# AQM_V1_Rev2.net
KiCad netlist of a schematic drawn in EasyEDA Pro
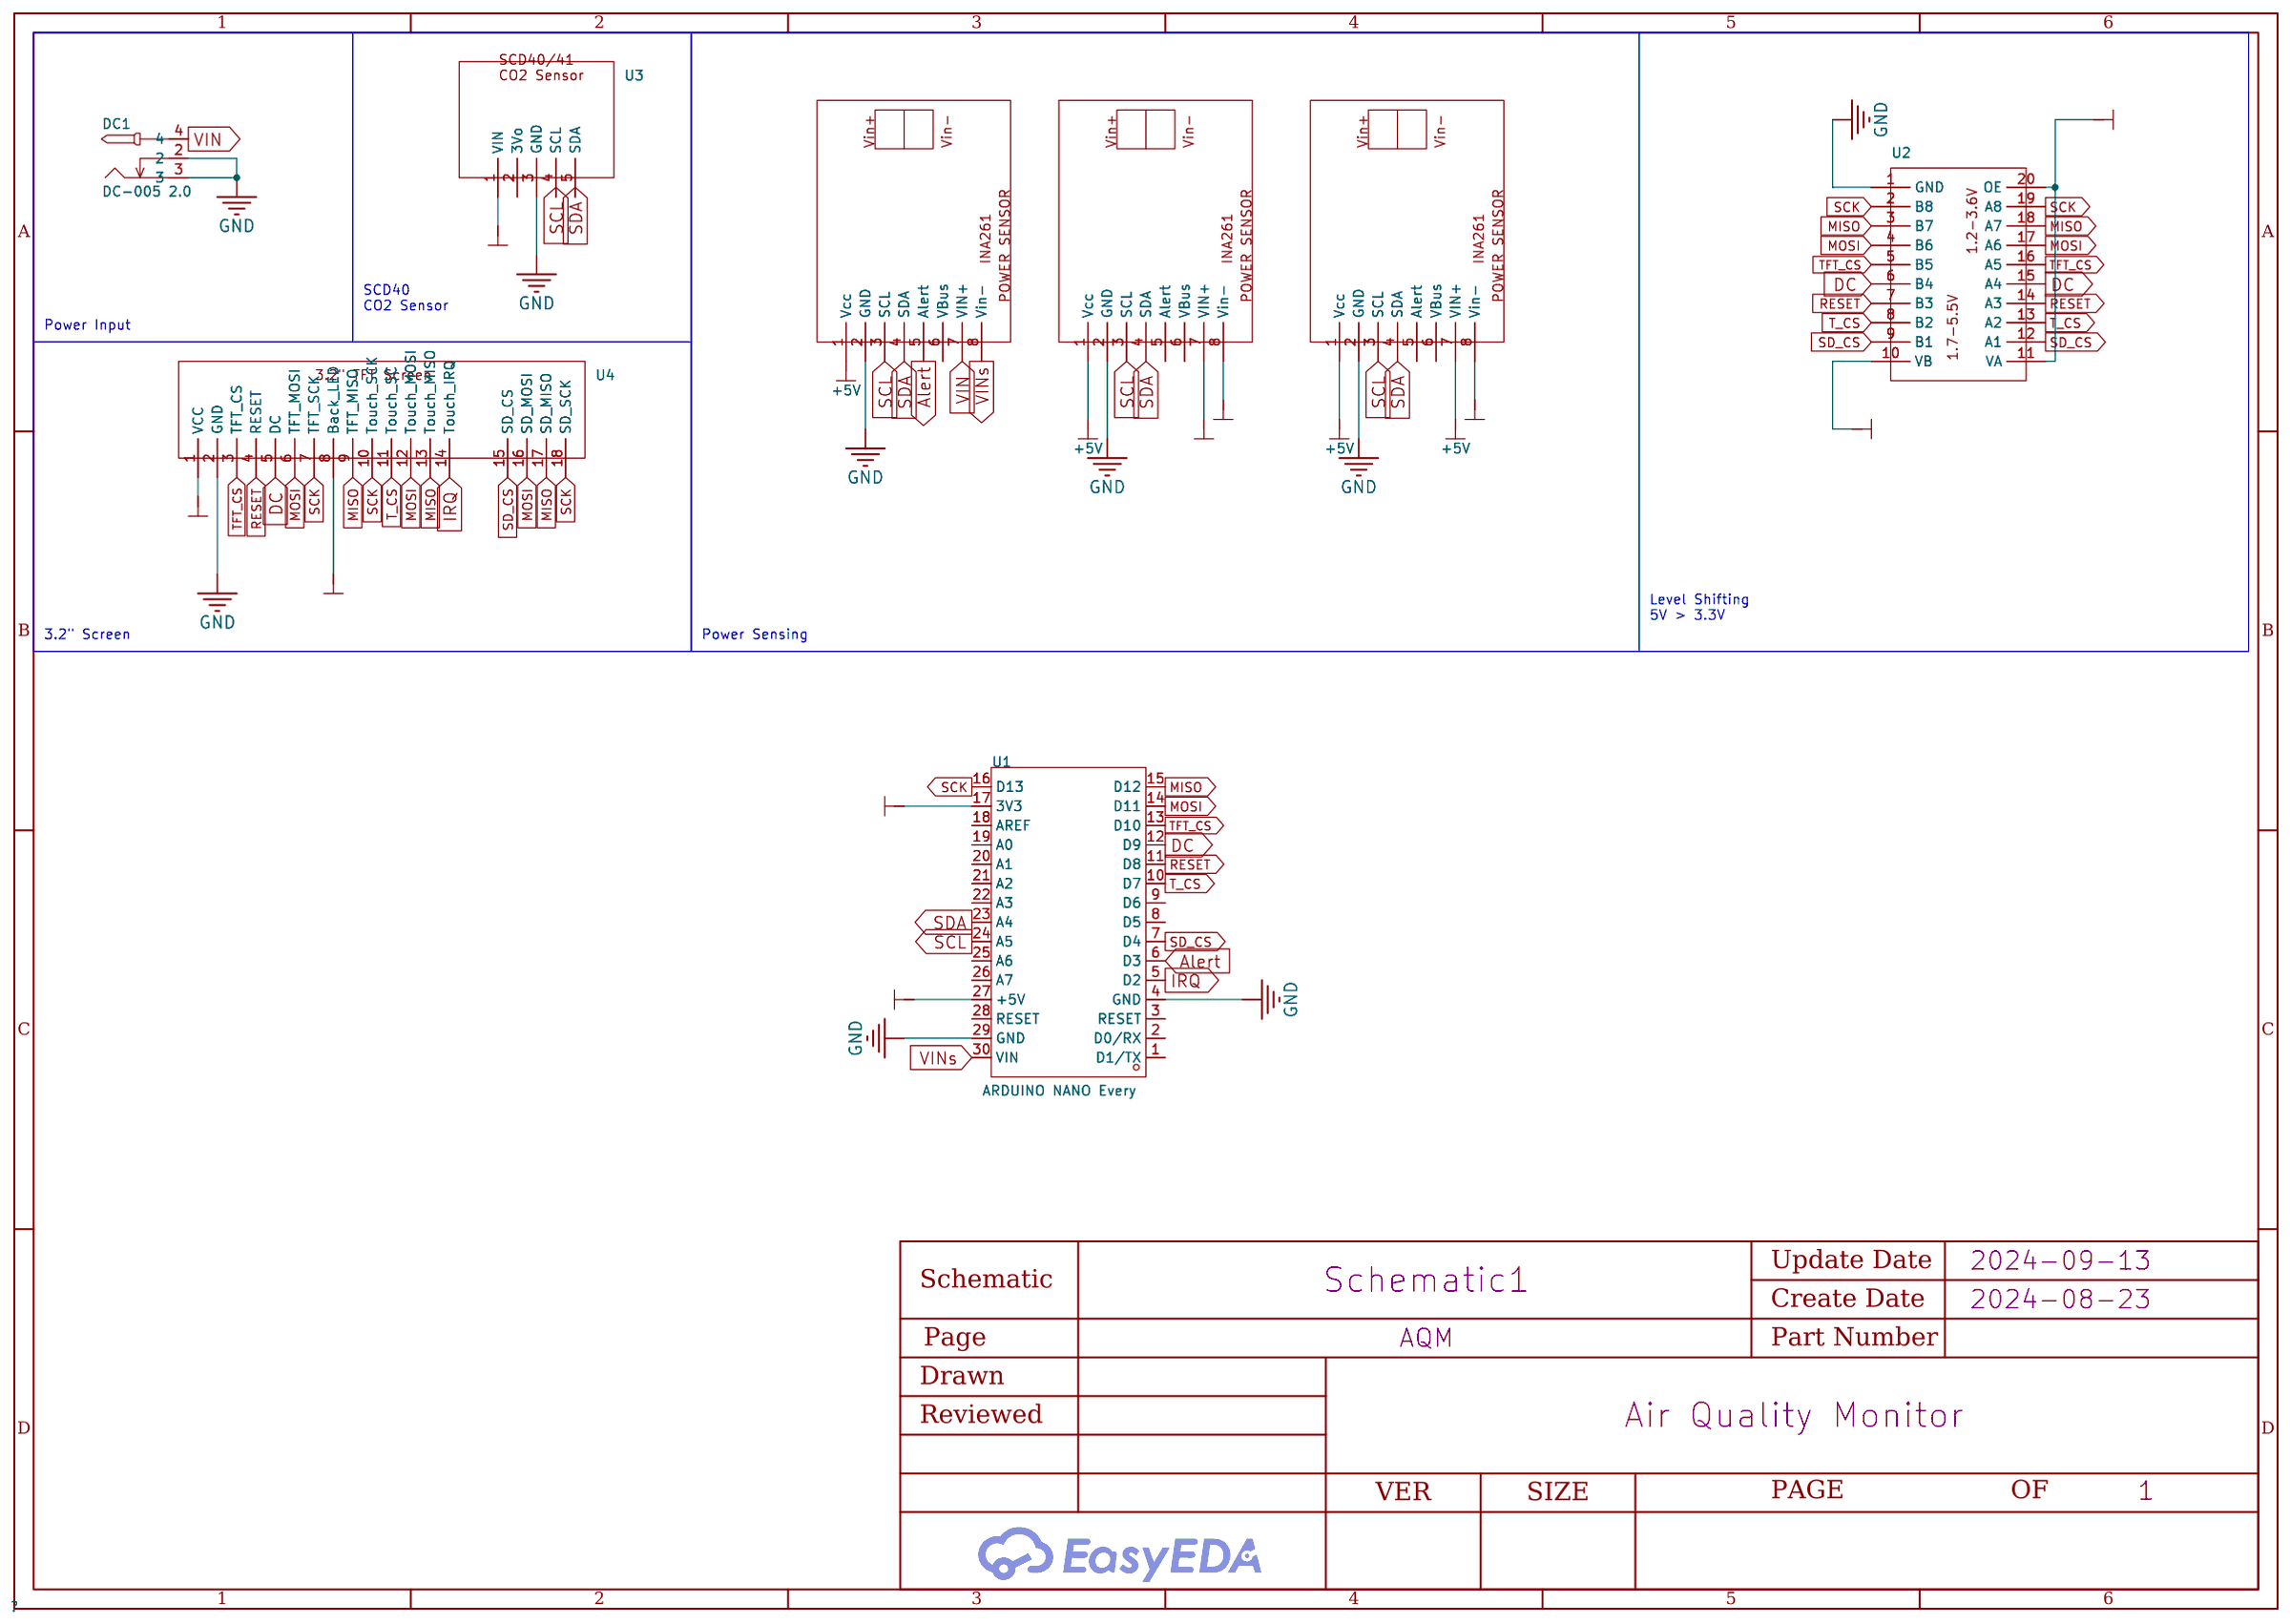
[diagram p0: schematic sheet]

(export (version "E")
  (design (tool "Eeschema 10.0.6"))
  (components
    (comp (ref "3.3V")
      (value "~")
      (footprint "easyedapro:INA260 Breakout")
      (description "Adafruit INA260 High or Low Side Voltage, Current, Power Sensor")
      (libsource (lib "easyedapro") (part "INA260 Breakout"))
    )
    (comp (ref "5V")
      (value "~")
      (footprint "easyedapro:INA260 Breakout")
      (description "Adafruit INA260 High or Low Side Voltage, Current, Power Sensor")
      (libsource (lib "easyedapro") (part "INA260 Breakout"))
    )
    (comp (ref "DC1")
      (value "DC-005 2.0")
      (footprint "easyedapro:DC-IN-TH_DC-5520-1")
      (fields (field (name "Manufacturer") "BOOMELE(博穆精密)"))
      (libsource (lib "easyedapro") (part "DC-005 5.5-2.0MM"))
    )
    (comp (ref "U1")
      (value "ARDUINO NANO Every")
      (footprint "easyedapro:COMM-TH_ARDUINO_NANO")
      (libsource (lib "easyedapro") (part "ARDUINO_NANO"))
    )
    (comp (ref "U2")
      (value "~")
      (footprint "easyedapro:8 Channel Level Shifter Footprint")
      (description "Level Shifter for 8 Channels from 3.3V to 5V")
      (libsource (lib "easyedapro") (part "8 Channel Level Shifter Symbol"))
    )
    (comp (ref "U3")
      (value "~")
      (footprint "easyedapro:Adafruit SCD40/41")
      (libsource (lib "easyedapro") (part "Adafruit SCD40/41 Breakout"))
    )
    (comp (ref "U4")
      (value "~")
      (footprint "easyedapro:2.8\" TFT Display Footprint 1")
      (description "2.8\" TFT Screen with SPI, Touch and SD Card.")
      (libsource (lib "easyedapro") (part "3.2{dblquote} TFT Screen Symbol"))
    )
    (comp (ref "VIN")
      (value "~")
      (footprint "easyedapro:INA260 Breakout")
      (description "Adafruit INA260 High or Low Side Voltage, Current, Power Sensor")
      (libsource (lib "easyedapro") (part "INA260 Breakout"))
    )
  )
  (nets
    (net (code "1") (name "+3V") (class "Default")
      (node (ref "3.3V") (pin "7") (pinfunction "VIN+_7") (pintype "input"))
      (node (ref "U1") (pin "17") (pinfunction "3V3_17") (pintype "unspecified"))
    )
    (net (code "2") (name "+3VS") (class "Default")
      (node (ref "3.3V") (pin "8") (pinfunction "Vin-_8") (pintype "input"))
      (node (ref "U2") (pin "11") (pinfunction "VA_11") (pintype "input"))
      (node (ref "U2") (pin "20") (pinfunction "OE_20") (pintype "input"))
      (node (ref "U4") (pin "8") (pinfunction "Back_LED_8") (pintype "input"))
    )
    (net (code "3") (name "+5V") (class "Default")
      (node (ref "3.3V") (pin "1") (pinfunction "Vcc_1") (pintype "input"))
      (node (ref "5V") (pin "1") (pinfunction "Vcc_1") (pintype "input"))
      (node (ref "5V") (pin "7") (pinfunction "VIN+_7") (pintype "input"))
      (node (ref "U1") (pin "27") (pinfunction "+5V_27") (pintype "unspecified"))
      (node (ref "VIN") (pin "1") (pinfunction "Vcc_1") (pintype "input"))
    )
    (net (code "4") (name "+5VS") (class "Default")
      (node (ref "5V") (pin "8") (pinfunction "Vin-_8") (pintype "input"))
      (node (ref "U2") (pin "10") (pinfunction "VB_10") (pintype "input"))
      (node (ref "U3") (pin "1") (pinfunction "VIN_1") (pintype "input"))
      (node (ref "U4") (pin "1") (pinfunction "VCC_1") (pintype "input"))
    )
    (net (code "5") (name "Alert") (class "Default")
      (node (ref "U1") (pin "6") (pinfunction "D3_6") (pintype "unspecified"))
      (node (ref "VIN") (pin "5") (pinfunction "Alert_5") (pintype "input"))
    )
    (net (code "6") (name "DC") (class "Default")
      (node (ref "U1") (pin "12") (pinfunction "D9_12") (pintype "unspecified"))
      (node (ref "U2") (pin "15") (pinfunction "A4_15") (pintype "input"))
      (node (ref "U2") (pin "6") (pinfunction "B4_6") (pintype "input"))
      (node (ref "U4") (pin "5") (pinfunction "DC_5") (pintype "input"))
    )
    (net (code "7") (name "GND") (class "Default")
      (node (ref "3.3V") (pin "2") (pinfunction "GND_2") (pintype "input"))
      (node (ref "5V") (pin "2") (pinfunction "GND_2") (pintype "input"))
      (node (ref "DC1") (pin "2") (pinfunction "2_2") (pintype "unspecified"))
      (node (ref "DC1") (pin "3") (pinfunction "3_3") (pintype "unspecified"))
      (node (ref "U1") (pin "29") (pinfunction "GND_29") (pintype "unspecified"))
      (node (ref "U1") (pin "4") (pinfunction "GND_4") (pintype "unspecified"))
      (node (ref "U2") (pin "1") (pinfunction "GND_1") (pintype "input"))
      (node (ref "U3") (pin "3") (pinfunction "GND_3") (pintype "input"))
      (node (ref "U4") (pin "2") (pinfunction "GND_2") (pintype "input"))
      (node (ref "VIN") (pin "2") (pinfunction "GND_2") (pintype "input"))
    )
    (net (code "8") (name "IRQ") (class "Default")
      (node (ref "U1") (pin "5") (pinfunction "D2_5") (pintype "unspecified"))
      (node (ref "U4") (pin "14") (pinfunction "Touch_IRQ_14") (pintype "input"))
    )
    (net (code "9") (name "MISO") (class "Default")
      (node (ref "U1") (pin "15") (pinfunction "D12_15") (pintype "unspecified"))
      (node (ref "U2") (pin "18") (pinfunction "A7_18") (pintype "input"))
      (node (ref "U2") (pin "3") (pinfunction "B7_3") (pintype "input"))
      (node (ref "U4") (pin "13") (pinfunction "Touch_MISO_13") (pintype "input"))
      (node (ref "U4") (pin "17") (pinfunction "SD_MISO_17") (pintype "input"))
      (node (ref "U4") (pin "9") (pinfunction "TFT_MISO_9") (pintype "input"))
    )
    (net (code "10") (name "MOSI") (class "Default")
      (node (ref "U1") (pin "14") (pinfunction "D11_14") (pintype "unspecified"))
      (node (ref "U2") (pin "17") (pinfunction "A6_17") (pintype "input"))
      (node (ref "U2") (pin "4") (pinfunction "B6_4") (pintype "input"))
      (node (ref "U4") (pin "12") (pinfunction "Touch_MOSI_12") (pintype "input"))
      (node (ref "U4") (pin "16") (pinfunction "SD_MOSI_16") (pintype "input"))
      (node (ref "U4") (pin "6") (pinfunction "TFT_MOSI_6") (pintype "input"))
    )
    (net (code "11") (name "RESET") (class "Default")
      (node (ref "U1") (pin "11") (pinfunction "D8_11") (pintype "unspecified"))
      (node (ref "U2") (pin "14") (pinfunction "A3_14") (pintype "input"))
      (node (ref "U2") (pin "7") (pinfunction "B3_7") (pintype "input"))
      (node (ref "U4") (pin "4") (pinfunction "RESET_4") (pintype "input"))
    )
    (net (code "12") (name "SCK") (class "Default")
      (node (ref "U1") (pin "16") (pinfunction "D13_16") (pintype "unspecified"))
      (node (ref "U2") (pin "19") (pinfunction "A8_19") (pintype "input"))
      (node (ref "U2") (pin "2") (pinfunction "B8_2") (pintype "input"))
      (node (ref "U4") (pin "10") (pinfunction "Touch_SCK_10") (pintype "input"))
      (node (ref "U4") (pin "18") (pinfunction "SD_SCK_18") (pintype "input"))
      (node (ref "U4") (pin "7") (pinfunction "TFT_SCK_7") (pintype "input"))
    )
    (net (code "13") (name "SCL") (class "Default")
      (node (ref "3.3V") (pin "3") (pinfunction "SCL_3") (pintype "input"))
      (node (ref "5V") (pin "3") (pinfunction "SCL_3") (pintype "input"))
      (node (ref "U1") (pin "24") (pinfunction "A5_24") (pintype "unspecified"))
      (node (ref "U3") (pin "4") (pinfunction "SCL_4") (pintype "input"))
      (node (ref "VIN") (pin "3") (pinfunction "SCL_3") (pintype "input"))
    )
    (net (code "14") (name "SDA") (class "Default")
      (node (ref "3.3V") (pin "4") (pinfunction "SDA_4") (pintype "input"))
      (node (ref "5V") (pin "4") (pinfunction "SDA_4") (pintype "input"))
      (node (ref "U1") (pin "23") (pinfunction "A4_23") (pintype "unspecified"))
      (node (ref "U3") (pin "5") (pinfunction "SDA_5") (pintype "input"))
      (node (ref "VIN") (pin "4") (pinfunction "SDA_4") (pintype "input"))
    )
    (net (code "15") (name "SD_CS") (class "Default")
      (node (ref "U1") (pin "7") (pinfunction "D4_7") (pintype "unspecified"))
      (node (ref "U2") (pin "12") (pinfunction "A1_12") (pintype "input"))
      (node (ref "U2") (pin "9") (pinfunction "B1_9") (pintype "input"))
      (node (ref "U4") (pin "15") (pinfunction "SD_CS_15") (pintype "input"))
    )
    (net (code "16") (name "TFT_CS") (class "Default")
      (node (ref "U1") (pin "13") (pinfunction "D10_13") (pintype "unspecified"))
      (node (ref "U2") (pin "16") (pinfunction "A5_16") (pintype "input"))
      (node (ref "U2") (pin "5") (pinfunction "B5_5") (pintype "input"))
      (node (ref "U4") (pin "3") (pinfunction "TFT_CS_3") (pintype "input"))
    )
    (net (code "17") (name "T_CS") (class "Default")
      (node (ref "U1") (pin "10") (pinfunction "D7_10") (pintype "unspecified"))
      (node (ref "U2") (pin "13") (pinfunction "A2_13") (pintype "input"))
      (node (ref "U2") (pin "8") (pinfunction "B2_8") (pintype "input"))
      (node (ref "U4") (pin "11") (pinfunction "Touch_SC_11") (pintype "input"))
    )
    (net (code "18") (name "VIN") (class "Default")
      (node (ref "DC1") (pin "4") (pinfunction "4_4") (pintype "unspecified"))
      (node (ref "VIN") (pin "7") (pinfunction "VIN+_7") (pintype "input"))
    )
    (net (code "19") (name "VINs") (class "Default")
      (node (ref "U1") (pin "30") (pinfunction "VIN_30") (pintype "unspecified"))
      (node (ref "VIN") (pin "8") (pinfunction "Vin-_8") (pintype "input"))
    )
    (net (code "20") (name "unconnected-(3.3V-Alert-Pad5)") (class "Default")
      (node (ref "3.3V") (pin "5") (pinfunction "Alert_5") (pintype "input"))
    )
    (net (code "21") (name "unconnected-(3.3V-VBus-Pad6)") (class "Default")
      (node (ref "3.3V") (pin "6") (pinfunction "VBus_6") (pintype "input"))
    )
    (net (code "22") (name "unconnected-(5V-Alert-Pad5)") (class "Default")
      (node (ref "5V") (pin "5") (pinfunction "Alert_5") (pintype "input"))
    )
    (net (code "23") (name "unconnected-(5V-VBus-Pad6)") (class "Default")
      (node (ref "5V") (pin "6") (pinfunction "VBus_6") (pintype "input"))
    )
    (net (code "24") (name "unconnected-(U1-A0-Pad19)") (class "Default")
      (node (ref "U1") (pin "19") (pinfunction "A0_19") (pintype "unspecified"))
    )
    (net (code "25") (name "unconnected-(U1-A1-Pad20)") (class "Default")
      (node (ref "U1") (pin "20") (pinfunction "A1_20") (pintype "unspecified"))
    )
    (net (code "26") (name "unconnected-(U1-A2-Pad21)") (class "Default")
      (node (ref "U1") (pin "21") (pinfunction "A2_21") (pintype "unspecified"))
    )
    (net (code "27") (name "unconnected-(U1-A3-Pad22)") (class "Default")
      (node (ref "U1") (pin "22") (pinfunction "A3_22") (pintype "unspecified"))
    )
    (net (code "28") (name "unconnected-(U1-A6-Pad25)") (class "Default")
      (node (ref "U1") (pin "25") (pinfunction "A6_25") (pintype "unspecified"))
    )
    (net (code "29") (name "unconnected-(U1-A7-Pad26)") (class "Default")
      (node (ref "U1") (pin "26") (pinfunction "A7_26") (pintype "unspecified"))
    )
    (net (code "30") (name "unconnected-(U1-AREF-Pad18)") (class "Default")
      (node (ref "U1") (pin "18") (pinfunction "AREF_18") (pintype "unspecified"))
    )
    (net (code "31") (name "unconnected-(U1-D0{slash}RX-Pad2)") (class "Default")
      (node (ref "U1") (pin "2") (pinfunction "D0/RX_2") (pintype "unspecified"))
    )
    (net (code "32") (name "unconnected-(U1-D1{slash}TX-Pad1)") (class "Default")
      (node (ref "U1") (pin "1") (pinfunction "D1/TX_1") (pintype "unspecified"))
    )
    (net (code "33") (name "unconnected-(U1-D5-Pad8)") (class "Default")
      (node (ref "U1") (pin "8") (pinfunction "D5_8") (pintype "unspecified"))
    )
    (net (code "34") (name "unconnected-(U1-D6-Pad9)") (class "Default")
      (node (ref "U1") (pin "9") (pinfunction "D6_9") (pintype "unspecified"))
    )
    (net (code "35") (name "unconnected-(U1-RESET-Pad3)") (class "Default")
      (node (ref "U1") (pin "3") (pinfunction "RESET_3") (pintype "unspecified"))
    )
    (net (code "36") (name "unconnected-(U1-RESET-Pad28)") (class "Default")
      (node (ref "U1") (pin "28") (pinfunction "RESET_28") (pintype "unspecified"))
    )
    (net (code "37") (name "unconnected-(U3-3Vo-Pad2)") (class "Default")
      (node (ref "U3") (pin "2") (pinfunction "3Vo_2") (pintype "input"))
    )
    (net (code "38") (name "unconnected-(VIN-VBus-Pad6)") (class "Default")
      (node (ref "VIN") (pin "6") (pinfunction "VBus_6") (pintype "input"))
    )
  )
)
